# design.net
KiCad netlist of a schematic drawn in Altium Designer
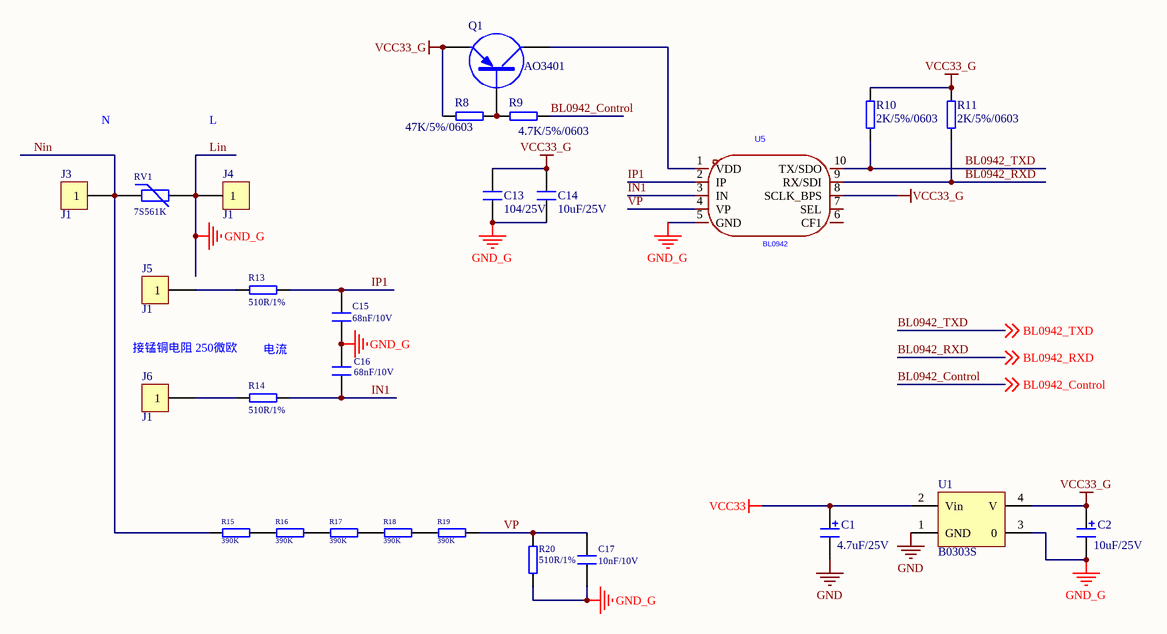
[diagram p0: 计量.SchDoc]

(export (version "E")
  (design (tool "Eeschema 10.0.6"))
  (components
    (comp (ref "C1") (value "4.7uF/25V") (footprint "0805R") (libsource (lib "ES_Schematic") (part "CAP+")))
    (comp (ref "C2") (value "10uF/25V") (footprint "0805R") (libsource (lib "ES_Schematic") (part "CAP+")))
    (comp (ref "C13") (value "104/25V") (footprint "0603R") (libsource (lib "ES_Schematic") (part "CAP_1")))
    (comp (ref "C14") (value "10uF/25V") (footprint "0603R") (libsource (lib "ES_Schematic") (part "CAP_1")))
    (comp (ref "C15") (value "68nF/10V") (footprint "0603R") (libsource (lib "ES_Schematic") (part "CAP")))
    (comp (ref "C16") (value "68nF/10V") (footprint "0603R") (libsource (lib "ES_Schematic") (part "CAP")))
    (comp (ref "C17") (value "10nF/10V") (footprint "0603R") (libsource (lib "ES_Schematic") (part "CAP")))
    (comp (ref "J3") (value "J1") (footprint "贴片焊盘V1（3*2椭圆）") (libsource (lib "ES_Schematic") (part "J1")))
    (comp (ref "J4") (value "J1") (footprint "贴片焊盘V1（3*2椭圆）") (libsource (lib "") (part "J1_1")))
    (comp (ref "J5") (value "J1") (footprint "贴片焊盘V1（3*2椭圆）") (libsource (lib "ES_Schematic") (part "J1")))
    (comp (ref "J6") (value "J1") (footprint "贴片焊盘V1（3*2椭圆）") (libsource (lib "ES_Schematic") (part "J1")))
    (comp (ref "Q1") (value "AO3401") (footprint "SOT-23") (libsource (lib "ES_Schematic") (part "PNP")))
    (comp (ref "R8") (value "47K/5%/0603") (footprint "0603R") (libsource (lib "ES_Schematic") (part "RES")))
    (comp (ref "R9") (value "4.7K/5%/0603") (footprint "0603R") (libsource (lib "ES_Schematic") (part "RES")))
    (comp (ref "R10") (value "2K/5%/0603") (footprint "0603R") (libsource (lib "ES_Schematic") (part "RES")))
    (comp (ref "R11") (value "2K/5%/0603") (footprint "0603R") (libsource (lib "ES_Schematic") (part "RES")))
    (comp (ref "R13") (value "510R/1%") (footprint "0603R") (libsource (lib "ES_Schematic") (part "RES")))
    (comp (ref "R14") (value "510R/1%") (footprint "0603R") (libsource (lib "ES_Schematic") (part "RES")))
    (comp (ref "R15") (value "390K") (footprint "0805R") (libsource (lib "ES_Schematic") (part "RES")))
    (comp (ref "R16") (value "390K") (footprint "0805R") (libsource (lib "ES_Schematic") (part "RES")))
    (comp (ref "R17") (value "390K") (footprint "0805R") (libsource (lib "ES_Schematic") (part "RES")))
    (comp (ref "R18") (value "390K") (footprint "0805R") (libsource (lib "ES_Schematic") (part "RES")))
    (comp (ref "R19") (value "390K") (footprint "0805R") (libsource (lib "ES_Schematic") (part "RES")))
    (comp (ref "R20") (value "510R/1%") (footprint "0603R") (libsource (lib "ES_Schematic") (part "RES")))
    (comp (ref "RV1")
      (value "7S561K")
      (footprint "10D821K")
      (description "Varistor (Voltage-Sensitive Resistor)")
      (fields (field (name "PUBLISHER") "Altium Limited"))
      (libsource (lib "Miscellaneous Devices") (part "Res Varistor"))
    )
    (comp (ref "U1") (value "B0303S") (footprint "B1205S-1WR3") (libsource (lib "sangjian") (part "B0505S")))
    (comp (ref "U5")
      (value "BL0942")
      (footprint "BL0942-10pin")
      (fields (field (name "MANUFACTURER") "BL(上海贝岭)"))
      (libsource (lib "altium-import") (part "root_0_BL0942_C2837510_"))
    )
  )
  (nets
    (net (code "1") (name "/IN1") (class "Default")
      (node (ref "C16") (pin "1") (pinfunction "1_1") (pintype "passive"))
      (node (ref "R14") (pin "2") (pinfunction "2_2") (pintype "passive"))
      (node (ref "U5") (pin "3") (pinfunction "IN_3") (pintype "passive"))
    )
    (net (code "2") (name "/IP1") (class "Default")
      (node (ref "C15") (pin "1") (pinfunction "1_1") (pintype "passive"))
      (node (ref "R13") (pin "2") (pinfunction "2_2") (pintype "passive"))
      (node (ref "U5") (pin "2") (pinfunction "IP_2") (pintype "passive"))
    )
    (net (code "3") (name "/Nin") (class "Default")
      (node (ref "J3") (pin "1") (pinfunction "1_1") (pintype "passive"))
      (node (ref "R15") (pin "2") (pinfunction "2_2") (pintype "passive"))
      (node (ref "RV1") (pin "1") (pinfunction "1_1") (pintype "passive"))
    )
    (net (code "4") (name "/VP") (class "Default")
      (node (ref "C17") (pin "1") (pinfunction "1_1") (pintype "passive"))
      (node (ref "R19") (pin "1") (pinfunction "1_1") (pintype "passive"))
      (node (ref "R20") (pin "2") (pinfunction "2_2") (pintype "passive"))
      (node (ref "U5") (pin "4") (pinfunction "VP_4") (pintype "passive"))
    )
    (net (code "5") (name "BL0942_Control") (class "Default")
      (node (ref "R9") (pin "2") (pinfunction "2_2") (pintype "passive"))
    )
    (net (code "6") (name "BL0942_RXD") (class "Default")
      (node (ref "R11") (pin "1") (pinfunction "1_1") (pintype "passive"))
      (node (ref "U5") (pin "9") (pinfunction "RX/SDI_9") (pintype "passive"))
    )
    (net (code "7") (name "BL0942_TXD") (class "Default")
      (node (ref "R10") (pin "1") (pinfunction "1_1") (pintype "passive"))
      (node (ref "U5") (pin "10") (pinfunction "TX/SDO_10") (pintype "passive"))
    )
    (net (code "8") (name "GND") (class "Default")
      (node (ref "C1") (pin "2") (pinfunction "2_2") (pintype "passive"))
      (node (ref "U1") (pin "1") (pinfunction "GND_1") (pintype "passive"))
    )
    (net (code "9") (name "GND_G") (class "Default")
      (node (ref "C13") (pin "1") (pinfunction "1_1") (pintype "passive"))
      (node (ref "C14") (pin "1") (pinfunction "1_1") (pintype "passive"))
      (node (ref "C15") (pin "2") (pinfunction "2_2") (pintype "passive"))
      (node (ref "C16") (pin "2") (pinfunction "2_2") (pintype "passive"))
      (node (ref "C17") (pin "2") (pinfunction "2_2") (pintype "passive"))
      (node (ref "C2") (pin "2") (pinfunction "2_2") (pintype "passive"))
      (node (ref "J4") (pin "1") (pinfunction "1_1") (pintype "passive"))
      (node (ref "R20") (pin "1") (pinfunction "1_1") (pintype "passive"))
      (node (ref "RV1") (pin "2") (pinfunction "2_2") (pintype "passive"))
      (node (ref "U1") (pin "3") (pinfunction "0_3") (pintype "passive"))
      (node (ref "U5") (pin "5") (pinfunction "GND_5") (pintype "passive"))
    )
    (net (code "10") (name "Net-(J5-Pad1)") (class "Default")
      (node (ref "J5") (pin "1") (pinfunction "1_1") (pintype "passive"))
      (node (ref "R13") (pin "1") (pinfunction "1_1") (pintype "passive"))
    )
    (net (code "11") (name "Net-(J6-Pad1)") (class "Default")
      (node (ref "J6") (pin "1") (pinfunction "1_1") (pintype "passive"))
      (node (ref "R14") (pin "1") (pinfunction "1_1") (pintype "passive"))
    )
    (net (code "12") (name "Net-(Q1-B)") (class "Default")
      (node (ref "Q1") (pin "1") (pinfunction "B_1") (pintype "passive"))
      (node (ref "R8") (pin "1") (pinfunction "1_1") (pintype "passive"))
      (node (ref "R9") (pin "1") (pinfunction "1_1") (pintype "passive"))
    )
    (net (code "13") (name "Net-(Q1-C)") (class "Default")
      (node (ref "Q1") (pin "3") (pinfunction "C_3") (pintype "passive"))
      (node (ref "U5") (pin "1") (pinfunction "VDD_1") (pintype "passive"))
    )
    (net (code "14") (name "Net-(R15-Pad1)") (class "Default")
      (node (ref "R15") (pin "1") (pinfunction "1_1") (pintype "passive"))
      (node (ref "R16") (pin "2") (pinfunction "2_2") (pintype "passive"))
    )
    (net (code "15") (name "Net-(R16-Pad1)") (class "Default")
      (node (ref "R16") (pin "1") (pinfunction "1_1") (pintype "passive"))
      (node (ref "R17") (pin "2") (pinfunction "2_2") (pintype "passive"))
    )
    (net (code "16") (name "Net-(R17-Pad1)") (class "Default")
      (node (ref "R17") (pin "1") (pinfunction "1_1") (pintype "passive"))
      (node (ref "R18") (pin "2") (pinfunction "2_2") (pintype "passive"))
    )
    (net (code "17") (name "Net-(R18-Pad1)") (class "Default")
      (node (ref "R18") (pin "1") (pinfunction "1_1") (pintype "passive"))
      (node (ref "R19") (pin "2") (pinfunction "2_2") (pintype "passive"))
    )
    (net (code "18") (name "VCC33") (class "Default")
      (node (ref "C1") (pin "1") (pinfunction "1_1") (pintype "passive"))
      (node (ref "U1") (pin "2") (pinfunction "Vin_2") (pintype "passive"))
    )
    (net (code "19") (name "VCC33_G") (class "Default")
      (node (ref "C13") (pin "2") (pinfunction "2_2") (pintype "passive"))
      (node (ref "C14") (pin "2") (pinfunction "2_2") (pintype "passive"))
      (node (ref "C2") (pin "1") (pinfunction "1_1") (pintype "passive"))
      (node (ref "Q1") (pin "2") (pinfunction "E_2") (pintype "passive"))
      (node (ref "R10") (pin "2") (pinfunction "2_2") (pintype "passive"))
      (node (ref "R11") (pin "2") (pinfunction "2_2") (pintype "passive"))
      (node (ref "R8") (pin "2") (pinfunction "2_2") (pintype "passive"))
      (node (ref "U1") (pin "4") (pinfunction "V_4") (pintype "passive"))
      (node (ref "U5") (pin "8") (pinfunction "SCLK_BPS_8") (pintype "passive"))
    )
    (net (code "20") (name "unconnected-(U5-CF1-Pad6)") (class "Default")
      (node (ref "U5") (pin "6") (pinfunction "CF1_6") (pintype "passive"))
    )
    (net (code "21") (name "unconnected-(U5-SEL-Pad7)") (class "Default")
      (node (ref "U5") (pin "7") (pinfunction "SEL_7") (pintype "passive"))
    )
  )
)
